# ISOLATED_PSU.net
KiCad netlist of a schematic drawn in Altium Designer
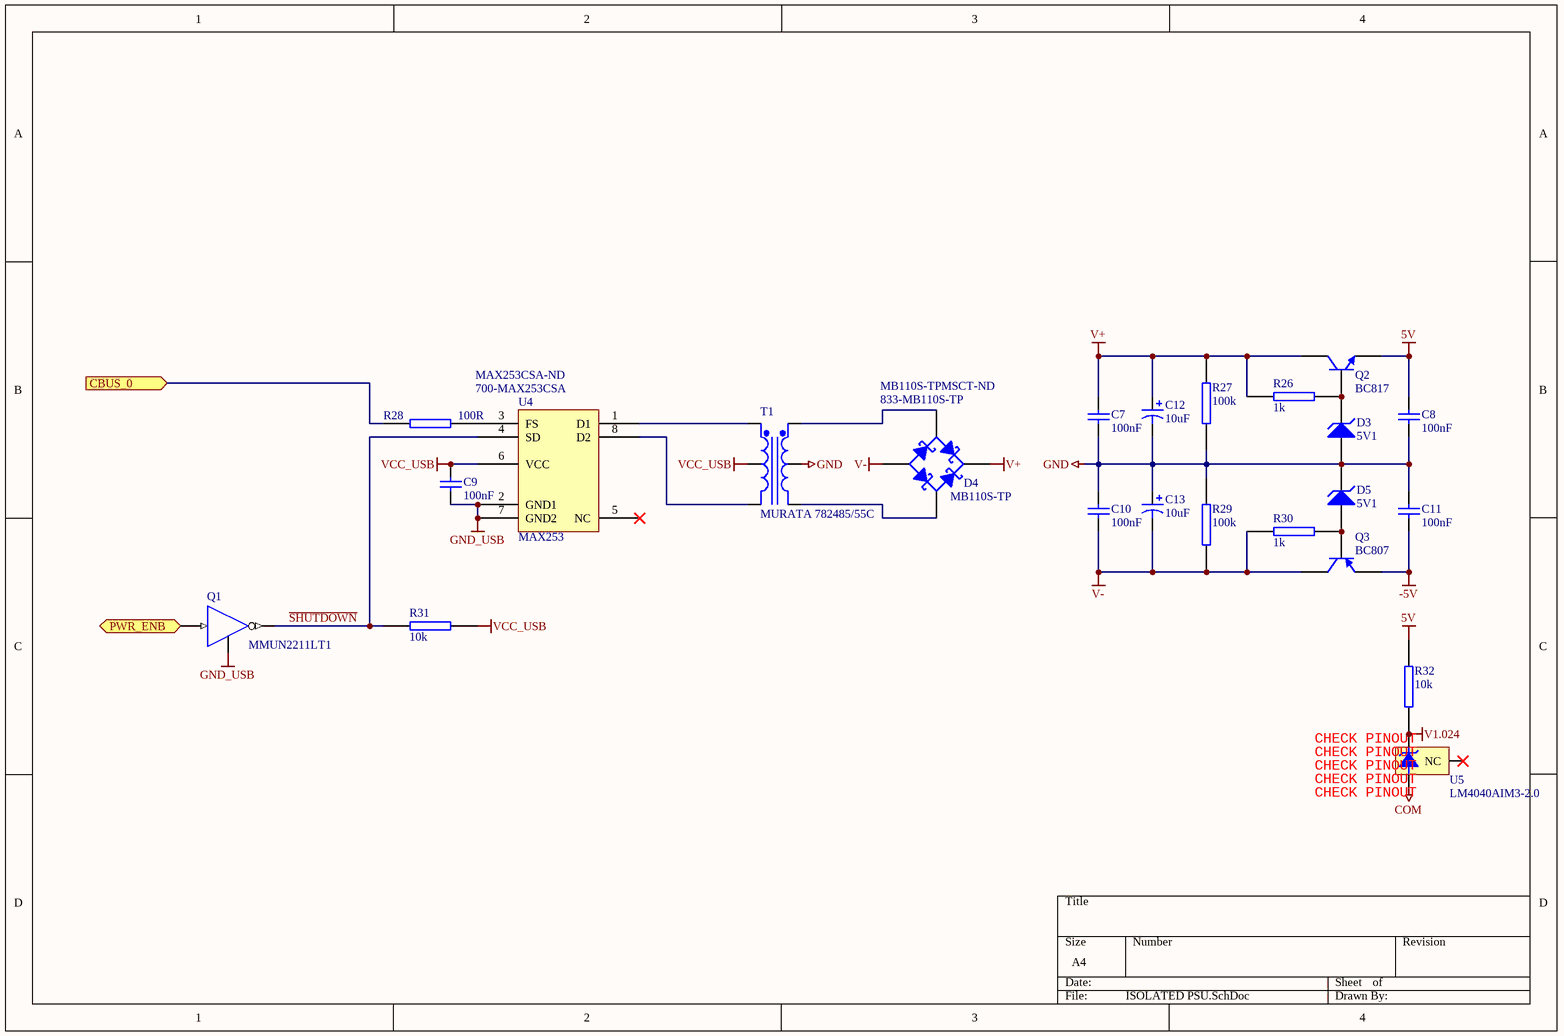
[diagram p0: ISOLATED PSU.SchDoc]

(export (version "E")
  (design (tool "Eeschema 10.0.6"))
  (components
    (comp (ref "C7")
      (value "100nF")
      (footprint "CAP (3D) - 0603")
      (description "Capacitor")
      (libsource (lib "Miscellaneous Devices") (part "Cap"))
    )
    (comp (ref "C8")
      (value "100nF")
      (footprint "CAP (3D) - 0603")
      (description "Capacitor")
      (libsource (lib "Miscellaneous Devices") (part "Cap"))
    )
    (comp (ref "C9")
      (value "100nF")
      (footprint "CAP (3D) - 0603")
      (description "Capacitor")
      (libsource (lib "Miscellaneous Devices") (part "Cap"))
    )
    (comp (ref "C10")
      (value "100nF")
      (footprint "CAP (3D) - 0603")
      (description "Capacitor")
      (libsource (lib "Miscellaneous Devices") (part "Cap"))
    )
    (comp (ref "C11")
      (value "100nF")
      (footprint "CAP (3D) - 0603")
      (description "Capacitor")
      (libsource (lib "Miscellaneous Devices") (part "Cap"))
    )
    (comp (ref "C12")
      (value "10uF")
      (footprint "CAP ELECTRO SIZE-B")
      (description "Polarized Capacitor (Radial)")
      (libsource (lib "Miscellaneous Devices") (part "Cap Pol1"))
    )
    (comp (ref "C13")
      (value "10uF")
      (footprint "CAP ELECTRO SIZE-B")
      (description "Polarized Capacitor (Radial)")
      (libsource (lib "Miscellaneous Devices") (part "Cap Pol1"))
    )
    (comp (ref "D3")
      (value "5V1")
      (footprint "SOT23-3L")
      (description "Zener Diode")
      (libsource (lib "Miscellaneous Devices") (part "D Zener"))
    )
    (comp (ref "D4")
      (value "MB110S-TP")
      (footprint "TO-269AA")
      (description "Full Wave Schottky Diode Bridge")
      (fields
        (field (name "SUPPLIER PART NUMBER 1") "833-MB110S-TP")
        (field (name "SUPPLIER PART NUMBER 2") "MB110S-TPMSCT-ND")
        (field (name "PUBLISHER") "Altium Limited")
      )
      (libsource (lib "Schlib1") (part "Bridge1"))
    )
    (comp (ref "D5")
      (value "5V1")
      (footprint "SOT23-3L")
      (description "Zener Diode")
      (libsource (lib "Miscellaneous Devices") (part "D Zener"))
    )
    (comp (ref "Q1")
      (value "MMUN2211LT1")
      (footprint "SOT23-3L")
      (fields
        (field (name "MOUSER PART NO.") "863-MMUN2211LT1G")
        (field (name "MANUFACTURER") "ON SEMO")
        (field (name "MANUFACTURER PART NO.") "MMUN2211LT1G")
      )
      (libsource (lib "401 CCPA") (part "NPN DIGITAL TRANSISTOR"))
    )
    (comp (ref "Q2")
      (value "BC817")
      (footprint "SOT23-3L")
      (description "NPN Bipolar Transistor")
      (fields
        (field (name "MANUFACTURER") "ON Semiconductor")
        (field (name "MOUSER PART NO.") "863-BC817-25LT1G")
      )
      (libsource (lib "NASCO") (part "BC817"))
    )
    (comp (ref "Q3")
      (value "BC807")
      (footprint "SOT23-3L")
      (description "PNP General Purpose Amplifier")
      (libsource (lib "Miscellaneous Devices") (part "2N3906"))
    )
    (comp (ref "R26")
      (value "1k")
      (footprint "RES (3D) - 0603")
      (description "RESISTOR SMD 0603")
      (libsource (lib "NASCO Resistors") (part "RES SMD 0603 100R"))
    )
    (comp (ref "R27")
      (value "100k")
      (footprint "RES (3D) - 0603")
      (description "RESISTOR SMD 0603")
      (libsource (lib "NASCO Resistors") (part "RES SMD 0603 100R"))
    )
    (comp (ref "R28")
      (value "100R")
      (footprint "RES (3D) - 0603")
      (description "RESISTOR SMD 0603")
      (libsource (lib "NASCO Resistors") (part "RES SMD 0603 100R"))
    )
    (comp (ref "R29")
      (value "100k")
      (footprint "RES (3D) - 0603")
      (description "RESISTOR SMD 0603")
      (libsource (lib "NASCO Resistors") (part "RES SMD 0603 100R"))
    )
    (comp (ref "R30")
      (value "1k")
      (footprint "RES (3D) - 0603")
      (description "RESISTOR SMD 0603")
      (libsource (lib "NASCO Resistors") (part "RES SMD 0603 100R"))
    )
    (comp (ref "R31")
      (value "10k")
      (footprint "RES (3D) - 0603")
      (description "RESISTOR SMD 0603")
      (libsource (lib "NASCO Resistors") (part "RES SMD 0603 100R"))
    )
    (comp (ref "R32")
      (value "10k")
      (footprint "RES (3D) - 0603")
      (description "RESISTOR SMD 0603 10k")
      (fields (field (name "MOUSER PART NO.") "652-CR0603FX-1002ELF") (field (name "MANUFACTURER") "Bourns"))
      (libsource (lib "NASCO Resistors") (part "RES SMD 0603 10k"))
    )
    (comp (ref "T1")
      (value "MURATA 782485/55C")
      (footprint "78248")
      (description "Center-Tapped Transformer (Coupled Inductor Model)")
      (fields (field (name "PUBLISHER") "Altium Limited"))
      (libsource (lib "Schlib1") (part "Trans CT"))
    )
    (comp (ref "U4")
      (value "MAX253")
      (footprint "SO-8C_L")
      (fields
        (field (name "SUPPLIER PART NUMBER 1") "700-MAX253CSA")
        (field (name "SUPPLIER PART NUMBER 2") "MAX253CSA-ND")
      )
      (libsource (lib "Schlib1") (part "MAX253"))
    )
    (comp (ref "U5")
      (value "LM4040AIM3-2.0")
      (footprint "SOT23-3L")
      (description "Precision Micropower Shunt Voltage Reference")
      (fields
        (field (name "MANUFACTURER") "National Semiconductor")
        (field (name "DIGIKEYPARTNUMBER") "LM4040AIM3-2.0-ND")
        (field (name "PUBLISHER") "Altium Limited")
      )
      (libsource (lib "NSC Voltage Reference") (part "LM4040AIM3-2.0"))
    )
  )
  (nets
    (net (code "1") (name "-5V") (class "Default")
      (node (ref "C11") (pin "1") (pinfunction "1_1") (pintype "passive"))
      (node (ref "Q3") (pin "1") (pinfunction "E_1") (pintype "passive"))
    )
    (net (code "2") (name "/CBUS_0") (class "Default")
      (node (ref "R28") (pin "1") (pinfunction "1_1") (pintype "passive"))
    )
    (net (code "3") (name "/PWR_ENB") (class "Default")
      (node (ref "Q1") (pin "1") (pinfunction "B_1") (pintype "input"))
    )
    (net (code "4") (name "/~{SHUTDOWN}") (class "Default")
      (node (ref "Q1") (pin "3") (pinfunction "C_3") (pintype "output"))
      (node (ref "R31") (pin "2") (pinfunction "2_2") (pintype "passive"))
      (node (ref "U4") (pin "4") (pinfunction "SD_4") (pintype "passive"))
    )
    (net (code "5") (name "5V") (class "Default")
      (node (ref "C8") (pin "2") (pinfunction "2_2") (pintype "passive"))
      (node (ref "Q2") (pin "3") (pinfunction "E_3") (pintype "passive"))
      (node (ref "R32") (pin "2") (pinfunction "2_2") (pintype "passive"))
    )
    (net (code "6") (name "COM") (class "Default")
      (node (ref "U5") (pin "2") (pinfunction "-V_2") (pintype "passive"))
    )
    (net (code "7") (name "GND") (class "Default")
      (node (ref "C10") (pin "2") (pinfunction "2_2") (pintype "passive"))
      (node (ref "C11") (pin "2") (pinfunction "2_2") (pintype "passive"))
      (node (ref "C12") (pin "2") (pinfunction "2_2") (pintype "passive"))
      (node (ref "C13") (pin "1") (pinfunction "1_1") (pintype "passive"))
      (node (ref "C7") (pin "1") (pinfunction "1_1") (pintype "passive"))
      (node (ref "C8") (pin "1") (pinfunction "1_1") (pintype "passive"))
      (node (ref "D3") (pin "1") (pinfunction "A_1") (pintype "passive"))
      (node (ref "D5") (pin "2") (pinfunction "K_2") (pintype "passive"))
      (node (ref "R27") (pin "2") (pinfunction "2_2") (pintype "passive"))
      (node (ref "R29") (pin "1") (pinfunction "1_1") (pintype "passive"))
      (node (ref "T1") (pin "5") (pinfunction "SecCT_5") (pintype "passive"))
    )
    (net (code "8") (name "GND_USB") (class "Default")
      (node (ref "C9") (pin "1") (pinfunction "1_1") (pintype "passive"))
      (node (ref "Q1") (pin "2") (pinfunction "E_2") (pintype "passive"))
      (node (ref "U4") (pin "2") (pinfunction "GND1_2") (pintype "passive"))
      (node (ref "U4") (pin "7") (pinfunction "GND2_7") (pintype "passive"))
    )
    (net (code "9") (name "Net-(D3-K)") (class "Default")
      (node (ref "D3") (pin "2") (pinfunction "K_2") (pintype "passive"))
      (node (ref "Q2") (pin "2") (pinfunction "B_2") (pintype "passive"))
      (node (ref "R26") (pin "1") (pinfunction "1_1") (pintype "passive"))
    )
    (net (code "10") (name "Net-(D5-A)") (class "Default")
      (node (ref "D5") (pin "1") (pinfunction "A_1") (pintype "passive"))
      (node (ref "Q3") (pin "2") (pinfunction "B_2") (pintype "passive"))
      (node (ref "R30") (pin "1") (pinfunction "1_1") (pintype "passive"))
    )
    (net (code "11") (name "Net-(T1-Pri+)") (class "Default")
      (node (ref "T1") (pin "1") (pinfunction "Pri+_1") (pintype "passive"))
      (node (ref "U4") (pin "1") (pinfunction "D1_1") (pintype "passive"))
    )
    (net (code "12") (name "Net-(T1-Pri-)") (class "Default")
      (node (ref "T1") (pin "3") (pinfunction "Pri-_3") (pintype "passive"))
      (node (ref "U4") (pin "8") (pinfunction "D2_8") (pintype "passive"))
    )
    (net (code "13") (name "Net-(T1-Sec+)") (class "Default")
      (node (ref "D4") (pin "4") (pinfunction "C_4") (pintype "passive"))
      (node (ref "T1") (pin "6") (pinfunction "Sec+_6") (pintype "passive"))
    )
    (net (code "14") (name "Net-(T1-Sec-)") (class "Default")
      (node (ref "D4") (pin "2") (pinfunction "C_2") (pintype "passive"))
      (node (ref "T1") (pin "4") (pinfunction "Sec-_4") (pintype "passive"))
    )
    (net (code "15") (name "Net-(U4-FS)") (class "Default")
      (node (ref "R28") (pin "2") (pinfunction "2_2") (pintype "passive"))
      (node (ref "U4") (pin "3") (pinfunction "FS_3") (pintype "passive"))
    )
    (net (code "16") (name "V+") (class "Default")
      (node (ref "C12") (pin "1") (pinfunction "1_1") (pintype "passive"))
      (node (ref "C7") (pin "2") (pinfunction "2_2") (pintype "passive"))
      (node (ref "D4") (pin "1") (pinfunction "K_1") (pintype "passive"))
      (node (ref "Q2") (pin "1") (pinfunction "C_1") (pintype "passive"))
      (node (ref "R26") (pin "2") (pinfunction "2_2") (pintype "passive"))
      (node (ref "R27") (pin "1") (pinfunction "1_1") (pintype "passive"))
    )
    (net (code "17") (name "V-") (class "Default")
      (node (ref "C10") (pin "1") (pinfunction "1_1") (pintype "passive"))
      (node (ref "C13") (pin "2") (pinfunction "2_2") (pintype "passive"))
      (node (ref "D4") (pin "3") (pinfunction "A_3") (pintype "passive"))
      (node (ref "Q3") (pin "3") (pinfunction "C_3") (pintype "passive"))
      (node (ref "R29") (pin "2") (pinfunction "2_2") (pintype "passive"))
      (node (ref "R30") (pin "2") (pinfunction "2_2") (pintype "passive"))
    )
    (net (code "18") (name "V1.024") (class "Default")
      (node (ref "R32") (pin "1") (pinfunction "1_1") (pintype "passive"))
      (node (ref "U5") (pin "1") (pinfunction "+V_1") (pintype "passive"))
    )
    (net (code "19") (name "VCC_USB") (class "Default")
      (node (ref "C9") (pin "2") (pinfunction "2_2") (pintype "passive"))
      (node (ref "R31") (pin "1") (pinfunction "1_1") (pintype "passive"))
      (node (ref "T1") (pin "2") (pinfunction "PriCT_2") (pintype "passive"))
      (node (ref "U4") (pin "6") (pinfunction "VCC_6") (pintype "passive"))
    )
    (net (code "20") (name "unconnected-(U4-NC-Pad5)") (class "Default")
      (node (ref "U4") (pin "5") (pinfunction "NC_5") (pintype "passive+no_connect"))
    )
    (net (code "21") (name "unconnected-(U5-NC-Pad3)") (class "Default")
      (node (ref "U5") (pin "3") (pinfunction "NC_3") (pintype "passive+no_connect"))
    )
  )
)
